# Rangkaian_minimumSystem.net
KiCad netlist of a schematic drawn in EAGLE
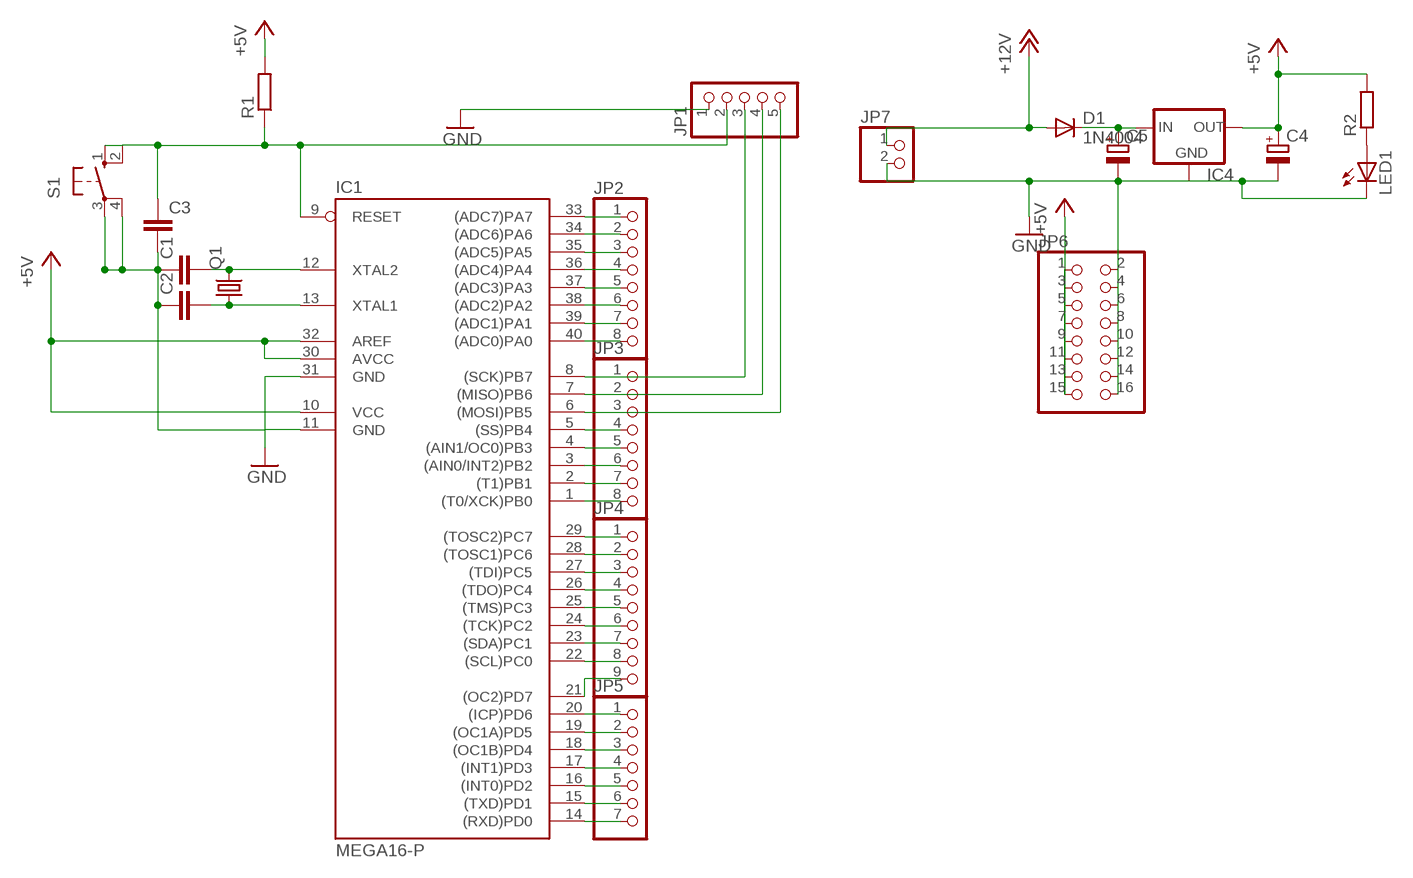
[diagram p0: schematic, sheet 1]

(export (version "E")
  (design (tool "Eeschema 10.0.6"))
  (components
    (comp (ref "C1")
      (value "C-EU025-024X044")
      (footprint "eagle-import:C025-024X044")
      (libsource (lib "eagle-import") (part "C-EU025-024X044"))
    )
    (comp (ref "C2")
      (value "C-EU025-024X044")
      (footprint "eagle-import:C025-024X044")
      (libsource (lib "eagle-import") (part "C-EU025-024X044"))
    )
    (comp (ref "C3")
      (value "C-EU050-025X075")
      (footprint "eagle-import:C050-025X075")
      (libsource (lib "eagle-import") (part "resistor_C-EU050-025X075"))
    )
    (comp (ref "C4")
      (value "CPOL-EUE2.5-5")
      (footprint "eagle-import:E2,5-5")
      (libsource (lib "eagle-import") (part "CPOL-EUE2.5-5"))
    )
    (comp (ref "C5")
      (value "CPOL-EUE2.5-5")
      (footprint "eagle-import:E2,5-5")
      (libsource (lib "eagle-import") (part "CPOL-EUE2.5-5"))
    )
    (comp (ref "D1")
      (value "1N4004")
      (footprint "eagle-import:DO41-10")
      (libsource (lib "eagle-import") (part "1N4004"))
    )
    (comp (ref "IC1")
      (value "MEGA16-P")
      (footprint "eagle-import:DIL40")
      (fields (field (name "MPN") "ATMEGA16-16PU"))
      (libsource (lib "eagle-import") (part "MEGA16-P"))
    )
    (comp (ref "IC4")
      (value "78XXS")
      (footprint "eagle-import:78XXS")
      (libsource (lib "eagle-import") (part "78XXS"))
    )
    (comp (ref "JP1")
      (value "PINHD-1X5")
      (footprint "eagle-import:1X05")
      (libsource (lib "eagle-import") (part "PINHD-1X5"))
    )
    (comp (ref "JP2")
      (value "PINHD-1X8")
      (footprint "eagle-import:1X08")
      (libsource (lib "eagle-import") (part "PINHD-1X8"))
    )
    (comp (ref "JP3")
      (value "PINHD-1X8")
      (footprint "eagle-import:1X08")
      (libsource (lib "eagle-import") (part "PINHD-1X8"))
    )
    (comp (ref "JP4")
      (value "PINHD-1X9")
      (footprint "eagle-import:1X09")
      (libsource (lib "eagle-import") (part "PINHD-1X9"))
    )
    (comp (ref "JP5")
      (value "PINHD-1X7")
      (footprint "eagle-import:1X07")
      (libsource (lib "eagle-import") (part "PINHD-1X7"))
    )
    (comp (ref "JP6")
      (value "PINHD-2X8")
      (footprint "eagle-import:2X08")
      (libsource (lib "eagle-import") (part "PINHD-2X8"))
    )
    (comp (ref "JP7")
      (value "PINHD-1X2")
      (footprint "eagle-import:1X02")
      (libsource (lib "eagle-import") (part "PINHD-1X2"))
    )
    (comp (ref "LED1")
      (value "LED5MM")
      (footprint "eagle-import:LED5MM")
      (libsource (lib "eagle-import") (part "LED5MM"))
    )
    (comp (ref "Q1")
      (value "CRYSTALHC49U-V")
      (footprint "eagle-import:HC49U-V")
      (libsource (lib "eagle-import") (part "CRYSTALHC49U-V"))
    )
    (comp (ref "R1")
      (value "R-EU_0204/7")
      (footprint "eagle-import:0204_7")
      (libsource (lib "eagle-import") (part "R-EU_0204/7"))
    )
    (comp (ref "R2")
      (value "R-EU_0204/7")
      (footprint "eagle-import:0204_7")
      (libsource (lib "eagle-import") (part "R-EU_0204/7"))
    )
    (comp (ref "S1")
      (value "10-XX")
      (footprint "eagle-import:B3F-10XX")
      (fields (field (name "MPN") "B3F-1000"))
      (libsource (lib "eagle-import") (part "10-XX"))
    )
  )
  (nets
    (net (code "1") (name "+5V") (class "Default")
      (node (ref "C4") (pin "+") (pinfunction "+_+") (pintype "passive"))
      (node (ref "IC1") (pin "10") (pinfunction "VCC_10") (pintype "power_in"))
      (node (ref "IC1") (pin "30") (pinfunction "AVCC_30") (pintype "power_in"))
      (node (ref "IC1") (pin "32") (pinfunction "AREF_32") (pintype "passive"))
      (node (ref "IC4") (pin "OUT") (pinfunction "OUT_OUT") (pintype "passive"))
      (node (ref "JP6") (pin "1") (pinfunction "1_1") (pintype "passive"))
      (node (ref "JP6") (pin "11") (pinfunction "11_11") (pintype "passive"))
      (node (ref "JP6") (pin "13") (pinfunction "13_13") (pintype "passive"))
      (node (ref "JP6") (pin "15") (pinfunction "15_15") (pintype "passive"))
      (node (ref "JP6") (pin "3") (pinfunction "3_3") (pintype "passive"))
      (node (ref "JP6") (pin "5") (pinfunction "5_5") (pintype "passive"))
      (node (ref "JP6") (pin "7") (pinfunction "7_7") (pintype "passive"))
      (node (ref "JP6") (pin "9") (pinfunction "9_9") (pintype "passive"))
      (node (ref "R1") (pin "2") (pinfunction "2_2") (pintype "passive"))
      (node (ref "R2") (pin "2") (pinfunction "2_2") (pintype "passive"))
    )
    (net (code "2") (name "+12V") (class "Default")
      (node (ref "D1") (pin "A") (pinfunction "A_A") (pintype "passive"))
      (node (ref "JP7") (pin "1") (pinfunction "1_1") (pintype "passive"))
    )
    (net (code "3") (name "GND") (class "Default")
      (node (ref "C1") (pin "1") (pinfunction "1_1") (pintype "passive"))
      (node (ref "C2") (pin "1") (pinfunction "1_1") (pintype "passive"))
      (node (ref "C3") (pin "2") (pinfunction "2_2") (pintype "passive"))
      (node (ref "C4") (pin "-") (pinfunction "-_-") (pintype "passive"))
      (node (ref "C5") (pin "-") (pinfunction "-_-") (pintype "passive"))
      (node (ref "IC1") (pin "11") (pinfunction "GND_11") (pintype "power_in"))
      (node (ref "IC1") (pin "31") (pinfunction "GND_31") (pintype "power_in"))
      (node (ref "IC4") (pin "GND") (pinfunction "GND_GND") (pintype "input"))
      (node (ref "JP1") (pin "1") (pinfunction "1_1") (pintype "passive"))
      (node (ref "JP6") (pin "10") (pinfunction "10_10") (pintype "passive"))
      (node (ref "JP6") (pin "12") (pinfunction "12_12") (pintype "passive"))
      (node (ref "JP6") (pin "14") (pinfunction "14_14") (pintype "passive"))
      (node (ref "JP6") (pin "16") (pinfunction "16_16") (pintype "passive"))
      (node (ref "JP6") (pin "2") (pinfunction "2_2") (pintype "passive"))
      (node (ref "JP6") (pin "4") (pinfunction "4_4") (pintype "passive"))
      (node (ref "JP6") (pin "6") (pinfunction "6_6") (pintype "passive"))
      (node (ref "JP6") (pin "8") (pinfunction "8_8") (pintype "passive"))
      (node (ref "JP7") (pin "2") (pinfunction "2_2") (pintype "passive"))
      (node (ref "LED1") (pin "K") (pinfunction "C_K") (pintype "passive"))
      (node (ref "S1") (pin "3") (pinfunction "P_3") (pintype "passive"))
      (node (ref "S1") (pin "4") (pinfunction "P1_4") (pintype "passive"))
    )
    (net (code "4") (name "Net-(C5-Pad+)") (class "Default")
      (node (ref "C5") (pin "+") (pinfunction "+_+") (pintype "passive"))
      (node (ref "D1") (pin "C") (pinfunction "C_C") (pintype "passive"))
      (node (ref "IC4") (pin "IN") (pinfunction "IN_IN") (pintype "input"))
    )
    (net (code "5") (name "Net-(IC1-(ADC0)PA0)") (class "Default")
      (node (ref "IC1") (pin "40") (pinfunction "(ADC0)PA0_40") (pintype "bidirectional"))
      (node (ref "JP2") (pin "8") (pinfunction "8_8") (pintype "passive"))
    )
    (net (code "6") (name "Net-(IC1-(ADC1)PA1)") (class "Default")
      (node (ref "IC1") (pin "39") (pinfunction "(ADC1)PA1_39") (pintype "bidirectional"))
      (node (ref "JP2") (pin "7") (pinfunction "7_7") (pintype "passive"))
    )
    (net (code "7") (name "Net-(IC1-(ADC2)PA2)") (class "Default")
      (node (ref "IC1") (pin "38") (pinfunction "(ADC2)PA2_38") (pintype "bidirectional"))
      (node (ref "JP2") (pin "6") (pinfunction "6_6") (pintype "passive"))
    )
    (net (code "8") (name "Net-(IC1-(ADC3)PA3)") (class "Default")
      (node (ref "IC1") (pin "37") (pinfunction "(ADC3)PA3_37") (pintype "bidirectional"))
      (node (ref "JP2") (pin "5") (pinfunction "5_5") (pintype "passive"))
    )
    (net (code "9") (name "Net-(IC1-(ADC4)PA4)") (class "Default")
      (node (ref "IC1") (pin "36") (pinfunction "(ADC4)PA4_36") (pintype "bidirectional"))
      (node (ref "JP2") (pin "4") (pinfunction "4_4") (pintype "passive"))
    )
    (net (code "10") (name "Net-(IC1-(ADC5)PA5)") (class "Default")
      (node (ref "IC1") (pin "35") (pinfunction "(ADC5)PA5_35") (pintype "bidirectional"))
      (node (ref "JP2") (pin "3") (pinfunction "3_3") (pintype "passive"))
    )
    (net (code "11") (name "Net-(IC1-(ADC6)PA6)") (class "Default")
      (node (ref "IC1") (pin "34") (pinfunction "(ADC6)PA6_34") (pintype "bidirectional"))
      (node (ref "JP2") (pin "2") (pinfunction "2_2") (pintype "passive"))
    )
    (net (code "12") (name "Net-(IC1-(ADC7)PA7)") (class "Default")
      (node (ref "IC1") (pin "33") (pinfunction "(ADC7)PA7_33") (pintype "bidirectional"))
      (node (ref "JP2") (pin "1") (pinfunction "1_1") (pintype "passive"))
    )
    (net (code "13") (name "Net-(IC1-(AIN0{slash}INT2)PB2)") (class "Default")
      (node (ref "IC1") (pin "3") (pinfunction "(AIN0/INT2)PB2_3") (pintype "bidirectional"))
      (node (ref "JP3") (pin "6") (pinfunction "6_6") (pintype "passive"))
    )
    (net (code "14") (name "Net-(IC1-(AIN1{slash}OC0)PB3)") (class "Default")
      (node (ref "IC1") (pin "4") (pinfunction "(AIN1/OC0)PB3_4") (pintype "bidirectional"))
      (node (ref "JP3") (pin "5") (pinfunction "5_5") (pintype "passive"))
    )
    (net (code "15") (name "Net-(IC1-(ICP)PD6)") (class "Default")
      (node (ref "IC1") (pin "20") (pinfunction "(ICP)PD6_20") (pintype "bidirectional"))
      (node (ref "JP5") (pin "1") (pinfunction "1_1") (pintype "passive"))
    )
    (net (code "16") (name "Net-(IC1-(INT0)PD2)") (class "Default")
      (node (ref "IC1") (pin "16") (pinfunction "(INT0)PD2_16") (pintype "bidirectional"))
      (node (ref "JP5") (pin "5") (pinfunction "5_5") (pintype "passive"))
    )
    (net (code "17") (name "Net-(IC1-(INT1)PD3)") (class "Default")
      (node (ref "IC1") (pin "17") (pinfunction "(INT1)PD3_17") (pintype "bidirectional"))
      (node (ref "JP5") (pin "4") (pinfunction "4_4") (pintype "passive"))
    )
    (net (code "18") (name "Net-(IC1-(MISO)PB6)") (class "Default")
      (node (ref "IC1") (pin "7") (pinfunction "(MISO)PB6_7") (pintype "bidirectional"))
      (node (ref "JP1") (pin "4") (pinfunction "4_4") (pintype "passive"))
      (node (ref "JP3") (pin "2") (pinfunction "2_2") (pintype "passive"))
    )
    (net (code "19") (name "Net-(IC1-(MOSI)PB5)") (class "Default")
      (node (ref "IC1") (pin "6") (pinfunction "(MOSI)PB5_6") (pintype "bidirectional"))
      (node (ref "JP1") (pin "5") (pinfunction "5_5") (pintype "passive"))
      (node (ref "JP3") (pin "3") (pinfunction "3_3") (pintype "passive"))
    )
    (net (code "20") (name "Net-(IC1-(OC1A)PD5)") (class "Default")
      (node (ref "IC1") (pin "19") (pinfunction "(OC1A)PD5_19") (pintype "bidirectional"))
      (node (ref "JP5") (pin "2") (pinfunction "2_2") (pintype "passive"))
    )
    (net (code "21") (name "Net-(IC1-(OC1B)PD4)") (class "Default")
      (node (ref "IC1") (pin "18") (pinfunction "(OC1B)PD4_18") (pintype "bidirectional"))
      (node (ref "JP5") (pin "3") (pinfunction "3_3") (pintype "passive"))
    )
    (net (code "22") (name "Net-(IC1-(OC2)PD7)") (class "Default")
      (node (ref "IC1") (pin "21") (pinfunction "(OC2)PD7_21") (pintype "bidirectional"))
      (node (ref "JP4") (pin "9") (pinfunction "9_9") (pintype "passive"))
    )
    (net (code "23") (name "Net-(IC1-(RXD)PD0)") (class "Default")
      (node (ref "IC1") (pin "14") (pinfunction "(RXD)PD0_14") (pintype "bidirectional"))
      (node (ref "JP5") (pin "7") (pinfunction "7_7") (pintype "passive"))
    )
    (net (code "24") (name "Net-(IC1-(SCK)PB7)") (class "Default")
      (node (ref "IC1") (pin "8") (pinfunction "(SCK)PB7_8") (pintype "bidirectional"))
      (node (ref "JP1") (pin "3") (pinfunction "3_3") (pintype "passive"))
      (node (ref "JP3") (pin "1") (pinfunction "1_1") (pintype "passive"))
    )
    (net (code "25") (name "Net-(IC1-(SCL)PC0)") (class "Default")
      (node (ref "IC1") (pin "22") (pinfunction "(SCL)PC0_22") (pintype "bidirectional"))
      (node (ref "JP4") (pin "8") (pinfunction "8_8") (pintype "passive"))
    )
    (net (code "26") (name "Net-(IC1-(SDA)PC1)") (class "Default")
      (node (ref "IC1") (pin "23") (pinfunction "(SDA)PC1_23") (pintype "bidirectional"))
      (node (ref "JP4") (pin "7") (pinfunction "7_7") (pintype "passive"))
    )
    (net (code "27") (name "Net-(IC1-(SS)PB4)") (class "Default")
      (node (ref "IC1") (pin "5") (pinfunction "(SS)PB4_5") (pintype "bidirectional"))
      (node (ref "JP3") (pin "4") (pinfunction "4_4") (pintype "passive"))
    )
    (net (code "28") (name "Net-(IC1-(T0{slash}XCK)PB0)") (class "Default")
      (node (ref "IC1") (pin "1") (pinfunction "(T0/XCK)PB0_1") (pintype "bidirectional"))
      (node (ref "JP3") (pin "8") (pinfunction "8_8") (pintype "passive"))
    )
    (net (code "29") (name "Net-(IC1-(T1)PB1)") (class "Default")
      (node (ref "IC1") (pin "2") (pinfunction "(T1)PB1_2") (pintype "bidirectional"))
      (node (ref "JP3") (pin "7") (pinfunction "7_7") (pintype "passive"))
    )
    (net (code "30") (name "Net-(IC1-(TCK)PC2)") (class "Default")
      (node (ref "IC1") (pin "24") (pinfunction "(TCK)PC2_24") (pintype "bidirectional"))
      (node (ref "JP4") (pin "6") (pinfunction "6_6") (pintype "passive"))
    )
    (net (code "31") (name "Net-(IC1-(TDI)PC5)") (class "Default")
      (node (ref "IC1") (pin "27") (pinfunction "(TDI)PC5_27") (pintype "bidirectional"))
      (node (ref "JP4") (pin "3") (pinfunction "3_3") (pintype "passive"))
    )
    (net (code "32") (name "Net-(IC1-(TDO)PC4)") (class "Default")
      (node (ref "IC1") (pin "26") (pinfunction "(TDO)PC4_26") (pintype "bidirectional"))
      (node (ref "JP4") (pin "4") (pinfunction "4_4") (pintype "passive"))
    )
    (net (code "33") (name "Net-(IC1-(TMS)PC3)") (class "Default")
      (node (ref "IC1") (pin "25") (pinfunction "(TMS)PC3_25") (pintype "bidirectional"))
      (node (ref "JP4") (pin "5") (pinfunction "5_5") (pintype "passive"))
    )
    (net (code "34") (name "Net-(IC1-(TOSC1)PC6)") (class "Default")
      (node (ref "IC1") (pin "28") (pinfunction "(TOSC1)PC6_28") (pintype "bidirectional"))
      (node (ref "JP4") (pin "2") (pinfunction "2_2") (pintype "passive"))
    )
    (net (code "35") (name "Net-(IC1-(TOSC2)PC7)") (class "Default")
      (node (ref "IC1") (pin "29") (pinfunction "(TOSC2)PC7_29") (pintype "bidirectional"))
      (node (ref "JP4") (pin "1") (pinfunction "1_1") (pintype "passive"))
    )
    (net (code "36") (name "Net-(IC1-(TXD)PD1)") (class "Default")
      (node (ref "IC1") (pin "15") (pinfunction "(TXD)PD1_15") (pintype "bidirectional"))
      (node (ref "JP5") (pin "6") (pinfunction "6_6") (pintype "passive"))
    )
    (net (code "37") (name "Net-(IC1-RESET)") (class "Default")
      (node (ref "C3") (pin "1") (pinfunction "1_1") (pintype "passive"))
      (node (ref "IC1") (pin "9") (pinfunction "RESET_9") (pintype "input"))
      (node (ref "JP1") (pin "2") (pinfunction "2_2") (pintype "passive"))
      (node (ref "R1") (pin "1") (pinfunction "1_1") (pintype "passive"))
      (node (ref "S1") (pin "1") (pinfunction "S_1") (pintype "passive"))
      (node (ref "S1") (pin "2") (pinfunction "S1_2") (pintype "passive"))
    )
    (net (code "38") (name "Net-(IC1-XTAL1)") (class "Default")
      (node (ref "C2") (pin "2") (pinfunction "2_2") (pintype "passive"))
      (node (ref "IC1") (pin "13") (pinfunction "XTAL1_13") (pintype "bidirectional"))
      (node (ref "Q1") (pin "1") (pinfunction "1_1") (pintype "passive"))
    )
    (net (code "39") (name "Net-(IC1-XTAL2)") (class "Default")
      (node (ref "C1") (pin "2") (pinfunction "2_2") (pintype "passive"))
      (node (ref "IC1") (pin "12") (pinfunction "XTAL2_12") (pintype "bidirectional"))
      (node (ref "Q1") (pin "2") (pinfunction "2_2") (pintype "passive"))
    )
    (net (code "40") (name "Net-(LED1-PadA)") (class "Default")
      (node (ref "LED1") (pin "A") (pinfunction "A_A") (pintype "passive"))
      (node (ref "R2") (pin "1") (pinfunction "1_1") (pintype "passive"))
    )
  )
)
